# LEDSlave_2.net
KiCad netlist of a schematic drawn in EAGLE
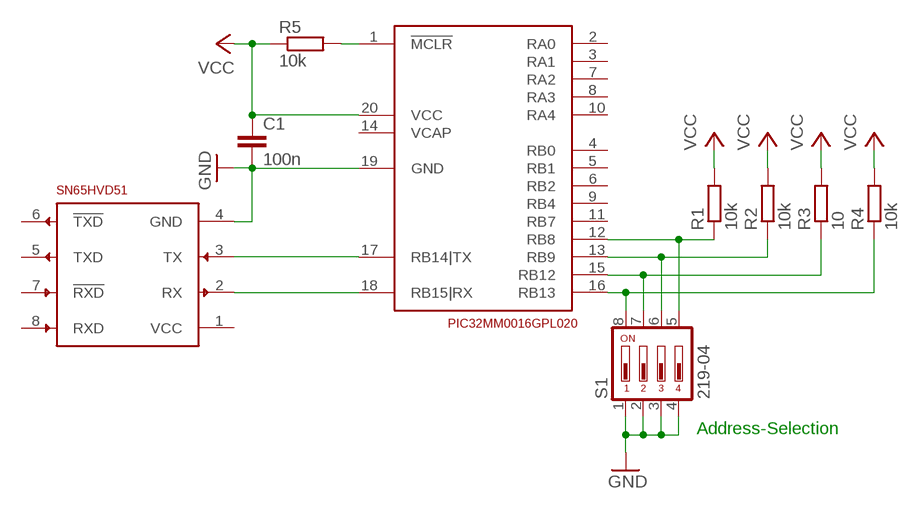
[diagram p0: schematic, sheet 1]

(export (version "E")
  (design (tool "Eeschema 10.0.6"))
  (components
    (comp (ref "C1")
      (value "100n")
      (footprint "eagle-import:C0805")
      (libsource (lib "eagle-import") (part "C-EUC0805"))
    )
    (comp (ref "R1")
      (value "10k")
      (footprint "eagle-import:R0805")
      (libsource (lib "eagle-import") (part "R-EU_R0805"))
    )
    (comp (ref "R2")
      (value "10k")
      (footprint "eagle-import:R0805")
      (libsource (lib "eagle-import") (part "R-EU_R0805"))
    )
    (comp (ref "R3")
      (value "10")
      (footprint "eagle-import:R0805")
      (libsource (lib "eagle-import") (part "R-EU_R0805"))
    )
    (comp (ref "R4")
      (value "10k")
      (footprint "eagle-import:R0805")
      (libsource (lib "eagle-import") (part "R-EU_R0805"))
    )
    (comp (ref "R5")
      (value "10k")
      (footprint "eagle-import:R0805")
      (libsource (lib "eagle-import") (part "R-EU_R0805"))
    )
    (comp (ref "S1")
      (value "219-04")
      (footprint "eagle-import:CTS-219-04")
      (libsource (lib "eagle-import") (part "219-04"))
    )
    (comp (ref "U$1")
      (value "PIC32MM0016GPL020")
      (footprint "eagle-import:SSOP20")
      (libsource (lib "eagle-import") (part "PIC32MM0016GPL020"))
    )
    (comp (ref "U$2")
      (value "SN65HVD51")
      (footprint "eagle-import:SO-08")
      (libsource (lib "eagle-import") (part "SN65HVD51"))
    )
  )
  (nets
    (net (code "1") (name "GND") (class "Default")
      (node (ref "C1") (pin "2") (pinfunction "2_2") (pintype "passive"))
      (node (ref "S1") (pin "1") (pinfunction "1_1") (pintype "passive"))
      (node (ref "S1") (pin "2") (pinfunction "2_2") (pintype "passive"))
      (node (ref "S1") (pin "3") (pinfunction "3_3") (pintype "passive"))
      (node (ref "S1") (pin "4") (pinfunction "4_4") (pintype "passive"))
      (node (ref "U$1") (pin "19") (pinfunction "GND_19") (pintype "bidirectional"))
      (node (ref "U$2") (pin "4") (pinfunction "GND_4") (pintype "bidirectional"))
    )
    (net (code "2") (name "Net-(U$1-RB8)") (class "Default")
      (node (ref "R1") (pin "1") (pinfunction "1_1") (pintype "passive"))
      (node (ref "S1") (pin "5") (pinfunction "5_5") (pintype "passive"))
      (node (ref "U$1") (pin "12") (pinfunction "RB8_12") (pintype "bidirectional"))
    )
    (net (code "3") (name "Net-(U$1-RB9)") (class "Default")
      (node (ref "R2") (pin "1") (pinfunction "1_1") (pintype "passive"))
      (node (ref "S1") (pin "6") (pinfunction "6_6") (pintype "passive"))
      (node (ref "U$1") (pin "13") (pinfunction "RB9_13") (pintype "bidirectional"))
    )
    (net (code "4") (name "Net-(U$1-RB12)") (class "Default")
      (node (ref "R3") (pin "1") (pinfunction "1_1") (pintype "passive"))
      (node (ref "S1") (pin "7") (pinfunction "7_7") (pintype "passive"))
      (node (ref "U$1") (pin "15") (pinfunction "RB12_15") (pintype "bidirectional"))
    )
    (net (code "5") (name "Net-(U$1-RB13)") (class "Default")
      (node (ref "R4") (pin "1") (pinfunction "1_1") (pintype "passive"))
      (node (ref "S1") (pin "8") (pinfunction "8_8") (pintype "passive"))
      (node (ref "U$1") (pin "16") (pinfunction "RB13_16") (pintype "bidirectional"))
    )
    (net (code "6") (name "Net-(U$1-RB14|TX)") (class "Default")
      (node (ref "U$1") (pin "17") (pinfunction "RB14|TX_17") (pintype "bidirectional"))
      (node (ref "U$2") (pin "3") (pinfunction "TX_3") (pintype "bidirectional"))
    )
    (net (code "7") (name "Net-(U$1-RB15|RX)") (class "Default")
      (node (ref "U$1") (pin "18") (pinfunction "RB15|RX_18") (pintype "bidirectional"))
      (node (ref "U$2") (pin "2") (pinfunction "RX_2") (pintype "bidirectional"))
    )
    (net (code "8") (name "Net-(U$1-~{MCLR})") (class "Default")
      (node (ref "R5") (pin "2") (pinfunction "2_2") (pintype "passive"))
      (node (ref "U$1") (pin "1") (pinfunction "~{MCLR}_1") (pintype "bidirectional"))
    )
    (net (code "9") (name "VCC") (class "Default")
      (node (ref "C1") (pin "1") (pinfunction "1_1") (pintype "passive"))
      (node (ref "R1") (pin "2") (pinfunction "2_2") (pintype "passive"))
      (node (ref "R2") (pin "2") (pinfunction "2_2") (pintype "passive"))
      (node (ref "R3") (pin "2") (pinfunction "2_2") (pintype "passive"))
      (node (ref "R4") (pin "2") (pinfunction "2_2") (pintype "passive"))
      (node (ref "R5") (pin "1") (pinfunction "1_1") (pintype "passive"))
      (node (ref "U$1") (pin "20") (pinfunction "VCC_20") (pintype "bidirectional"))
    )
    (net (code "10") (name "unconnected-(U$1-RA0-Pad2)") (class "Default")
      (node (ref "U$1") (pin "2") (pinfunction "RA0_2") (pintype "bidirectional"))
    )
    (net (code "11") (name "unconnected-(U$1-RA1-Pad3)") (class "Default")
      (node (ref "U$1") (pin "3") (pinfunction "RA1_3") (pintype "bidirectional"))
    )
    (net (code "12") (name "unconnected-(U$1-RA2-Pad7)") (class "Default")
      (node (ref "U$1") (pin "7") (pinfunction "RA2_7") (pintype "bidirectional"))
    )
    (net (code "13") (name "unconnected-(U$1-RA3-Pad8)") (class "Default")
      (node (ref "U$1") (pin "8") (pinfunction "RA3_8") (pintype "bidirectional"))
    )
    (net (code "14") (name "unconnected-(U$1-RA4-Pad10)") (class "Default")
      (node (ref "U$1") (pin "10") (pinfunction "RA4_10") (pintype "bidirectional"))
    )
    (net (code "15") (name "unconnected-(U$1-RB0-Pad4)") (class "Default")
      (node (ref "U$1") (pin "4") (pinfunction "RB0_4") (pintype "bidirectional"))
    )
    (net (code "16") (name "unconnected-(U$1-RB1-Pad5)") (class "Default")
      (node (ref "U$1") (pin "5") (pinfunction "RB1_5") (pintype "bidirectional"))
    )
    (net (code "17") (name "unconnected-(U$1-RB2-Pad6)") (class "Default")
      (node (ref "U$1") (pin "6") (pinfunction "RB2_6") (pintype "bidirectional"))
    )
    (net (code "18") (name "unconnected-(U$1-RB4-Pad9)") (class "Default")
      (node (ref "U$1") (pin "9") (pinfunction "RB4_9") (pintype "bidirectional"))
    )
    (net (code "19") (name "unconnected-(U$1-RB7-Pad11)") (class "Default")
      (node (ref "U$1") (pin "11") (pinfunction "RB7_11") (pintype "bidirectional"))
    )
    (net (code "20") (name "unconnected-(U$1-VCAP-Pad14)") (class "Default")
      (node (ref "U$1") (pin "14") (pinfunction "VCAP_14") (pintype "bidirectional"))
    )
    (net (code "21") (name "unconnected-(U$2-RXD-Pad8)") (class "Default")
      (node (ref "U$2") (pin "8") (pinfunction "RXD_8") (pintype "bidirectional"))
    )
    (net (code "22") (name "unconnected-(U$2-TXD-Pad5)") (class "Default")
      (node (ref "U$2") (pin "5") (pinfunction "TXD_5") (pintype "bidirectional"))
    )
    (net (code "23") (name "unconnected-(U$2-VCC-Pad1)") (class "Default")
      (node (ref "U$2") (pin "1") (pinfunction "VCC_1") (pintype "bidirectional"))
    )
    (net (code "24") (name "unconnected-(U$2-~{RXD}-Pad7)") (class "Default")
      (node (ref "U$2") (pin "7") (pinfunction "~{RXD}_7") (pintype "bidirectional"))
    )
    (net (code "25") (name "unconnected-(U$2-~{TXD}-Pad6)") (class "Default")
      (node (ref "U$2") (pin "6") (pinfunction "~{TXD}_6") (pintype "bidirectional"))
    )
  )
)
